# NanoTrac.net
KiCad netlist of a schematic drawn in EAGLE
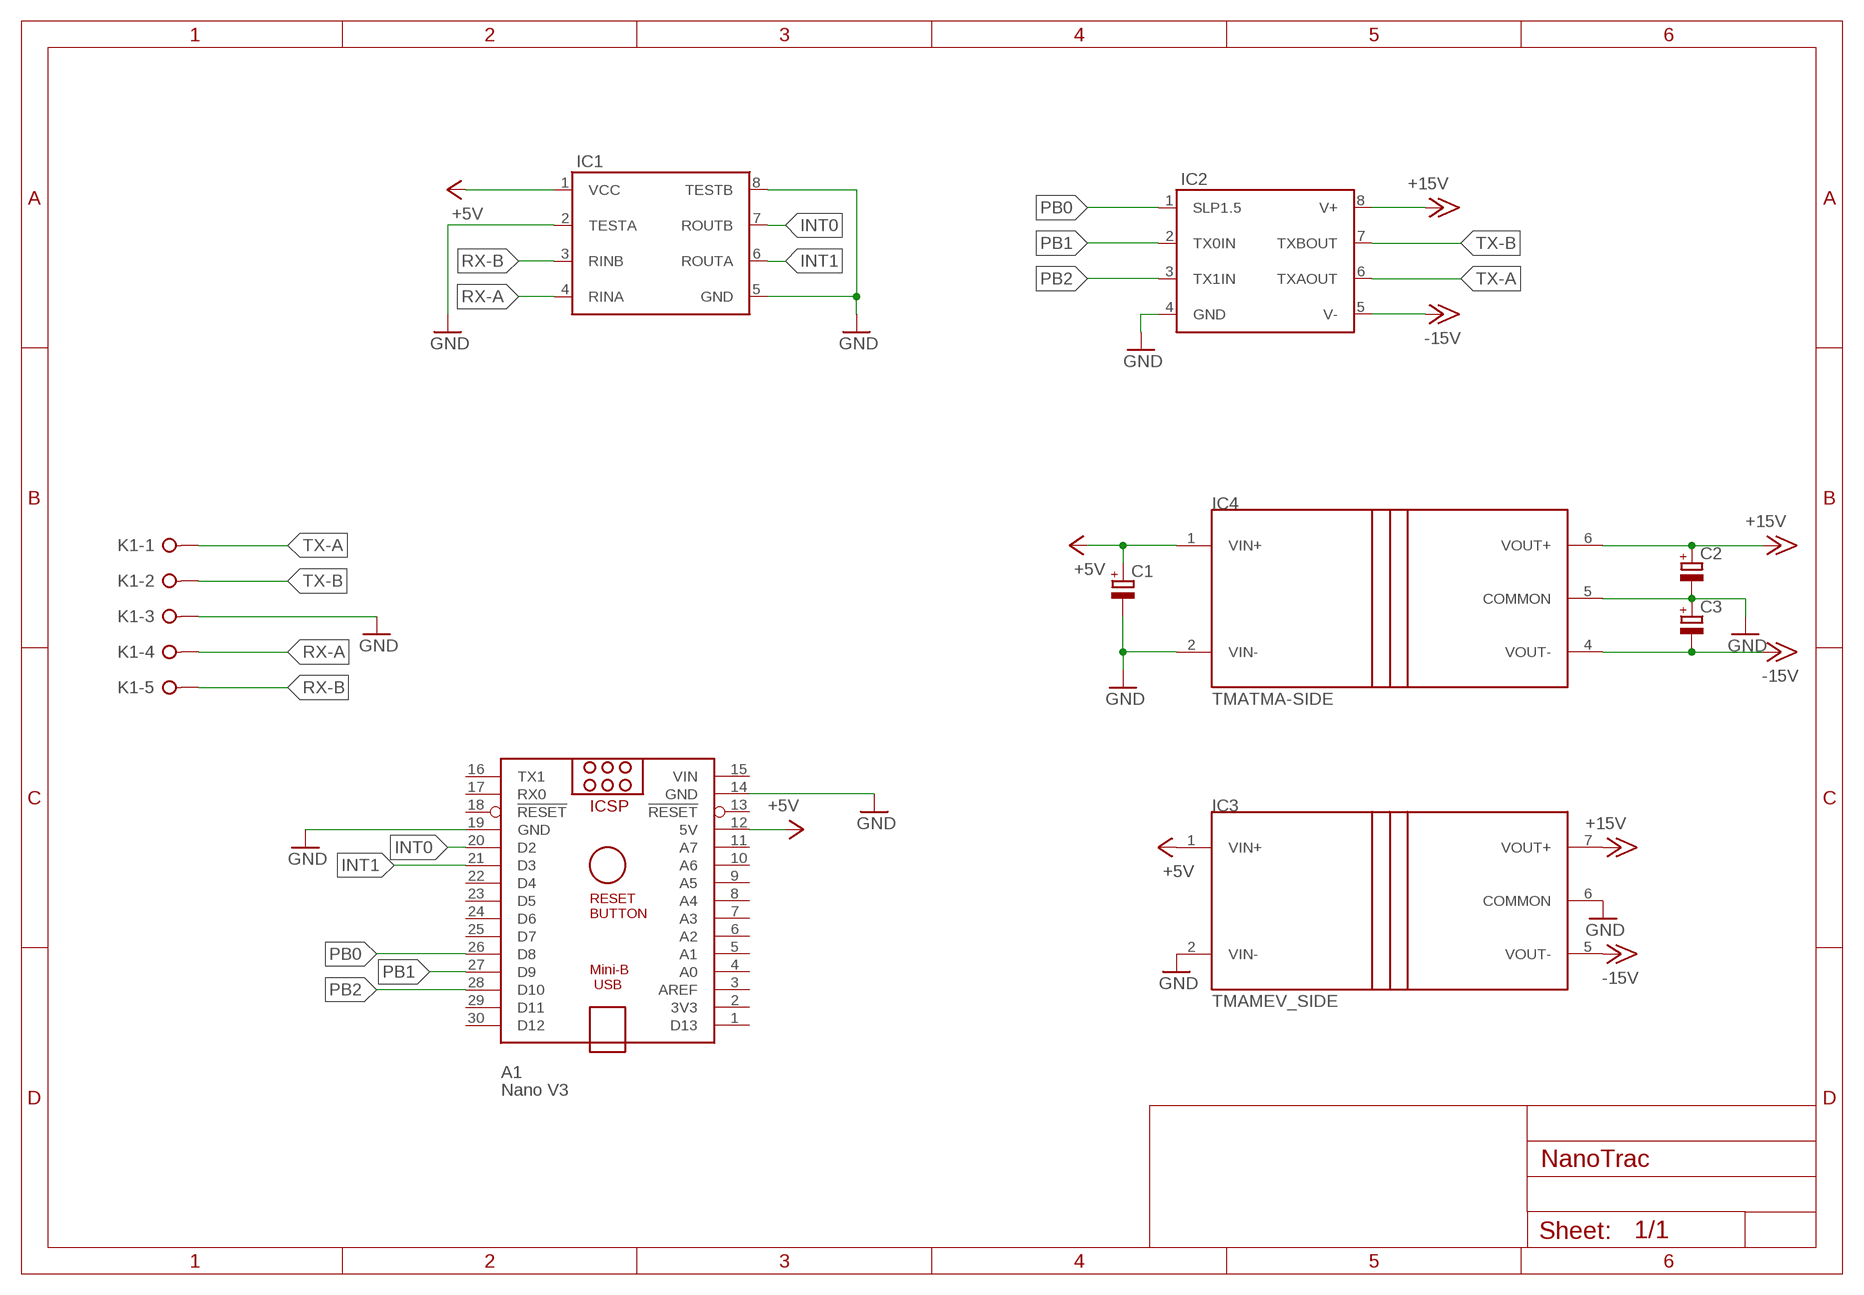
[diagram p0: schematic, sheet 1]

(export (version "E")
  (design (tool "Eeschema 10.0.6"))
  (components
    (comp (ref "A1")
      (value "Nano V3")
      (footprint "eagle-import:ARDUINO_NANO")
      (libsource (lib "eagle-import") (part "ARDUINO_NANO"))
    )
    (comp (ref "C1")
      (value "CPOL-EUE2-4")
      (footprint "eagle-import:E2-4")
      (libsource (lib "eagle-import") (part "CPOL-EUE2-4"))
    )
    (comp (ref "C2")
      (value "CPOL-EUE2-4")
      (footprint "eagle-import:E2-4")
      (libsource (lib "eagle-import") (part "CPOL-EUE2-4"))
    )
    (comp (ref "C3")
      (value "CPOL-EUE2-4")
      (footprint "eagle-import:E2-4")
      (libsource (lib "eagle-import") (part "CPOL-EUE2-4"))
    )
    (comp (ref "IC1")
      (value "HI-8588HN")
      (footprint "eagle-import:SOIC8")
      (libsource (lib "eagle-import") (part "HI-8588HN"))
    )
    (comp (ref "IC2")
      (value "HI-8586HN")
      (footprint "eagle-import:SOIC8")
      (libsource (lib "eagle-import") (part "HI-8586HN"))
    )
    (comp (ref "IC3")
      (value "TMAMEV_SIDE")
      (footprint "eagle-import:MEV_SIP7_SIDE")
      (libsource (lib "eagle-import") (part "TMAMEV_SIDE"))
    )
    (comp (ref "IC4")
      (value "TMATMA-SIDE")
      (footprint "eagle-import:SIP7_SIDE")
      (libsource (lib "eagle-import") (part "TMATMA-SIDE"))
    )
    (comp (ref "K1")
      (value "W237-05P")
      (footprint "eagle-import:W237-5P")
      (libsource (lib "eagle-import") (part "W237-05P"))
    )
  )
  (nets
    (net (code "1") (name "+5V") (class "Default")
      (node (ref "A1") (pin "12") (pinfunction "5V_12") (pintype "power_in"))
      (node (ref "C1") (pin "+") (pinfunction "+_+") (pintype "passive"))
      (node (ref "IC1") (pin "1") (pinfunction "VCC_1") (pintype "power_in"))
      (node (ref "IC3") (pin "1") (pinfunction "VIN+_1") (pintype "power_in"))
      (node (ref "IC4") (pin "1") (pinfunction "VIN+_1") (pintype "power_in"))
    )
    (net (code "2") (name "+15V") (class "Default")
      (node (ref "C2") (pin "+") (pinfunction "+_+") (pintype "passive"))
      (node (ref "IC2") (pin "8") (pinfunction "V+_8") (pintype "power_in"))
      (node (ref "IC3") (pin "7") (pinfunction "VOUT+_7") (pintype "power_in"))
      (node (ref "IC4") (pin "6") (pinfunction "VOUT+_6") (pintype "power_in"))
    )
    (net (code "3") (name "-15V") (class "Default")
      (node (ref "C3") (pin "-") (pinfunction "-_-") (pintype "passive"))
      (node (ref "IC2") (pin "5") (pinfunction "V-_5") (pintype "power_in"))
      (node (ref "IC3") (pin "5") (pinfunction "VOUT-_5") (pintype "power_in"))
      (node (ref "IC4") (pin "4") (pinfunction "VOUT-_4") (pintype "power_in"))
    )
    (net (code "4") (name "/VIN") (class "Default")
      (node (ref "A1") (pin "15") (pinfunction "VIN_15") (pintype "power_in"))
    )
    (net (code "5") (name "GND") (class "Default")
      (node (ref "A1") (pin "14") (pinfunction "GND_14") (pintype "power_in"))
      (node (ref "A1") (pin "19") (pinfunction "GND_19") (pintype "power_in"))
      (node (ref "C1") (pin "-") (pinfunction "-_-") (pintype "passive"))
      (node (ref "C2") (pin "-") (pinfunction "-_-") (pintype "passive"))
      (node (ref "C3") (pin "+") (pinfunction "+_+") (pintype "passive"))
      (node (ref "IC1") (pin "2") (pinfunction "TESTA_2") (pintype "input"))
      (node (ref "IC1") (pin "5") (pinfunction "GND_5") (pintype "passive"))
      (node (ref "IC1") (pin "8") (pinfunction "TESTB_8") (pintype "input"))
      (node (ref "IC2") (pin "4") (pinfunction "GND_4") (pintype "passive"))
      (node (ref "IC3") (pin "2") (pinfunction "VIN-_2") (pintype "power_in"))
      (node (ref "IC3") (pin "6") (pinfunction "COMMON_6") (pintype "power_in"))
      (node (ref "IC4") (pin "2") (pinfunction "VIN-_2") (pintype "power_in"))
      (node (ref "IC4") (pin "5") (pinfunction "COMMON_5") (pintype "power_in"))
      (node (ref "K1") (pin "3") (pinfunction "KL_3") (pintype "passive"))
    )
    (net (code "6") (name "INT0") (class "Default")
      (node (ref "A1") (pin "20") (pinfunction "D2_20") (pintype "bidirectional"))
      (node (ref "IC1") (pin "7") (pinfunction "ROUTB_7") (pintype "output"))
    )
    (net (code "7") (name "INT1") (class "Default")
      (node (ref "A1") (pin "21") (pinfunction "D3_21") (pintype "bidirectional"))
      (node (ref "IC1") (pin "6") (pinfunction "ROUTA_6") (pintype "output"))
    )
    (net (code "8") (name "PB0") (class "Default")
      (node (ref "A1") (pin "26") (pinfunction "D8_26") (pintype "bidirectional"))
      (node (ref "IC2") (pin "1") (pinfunction "SLP1.5_1") (pintype "input"))
    )
    (net (code "9") (name "PB1") (class "Default")
      (node (ref "A1") (pin "27") (pinfunction "D9_27") (pintype "bidirectional"))
      (node (ref "IC2") (pin "2") (pinfunction "TX0IN_2") (pintype "input"))
    )
    (net (code "10") (name "PB2") (class "Default")
      (node (ref "A1") (pin "28") (pinfunction "D10_28") (pintype "bidirectional"))
      (node (ref "IC2") (pin "3") (pinfunction "TX1IN_3") (pintype "input"))
    )
    (net (code "11") (name "RX-A") (class "Default")
      (node (ref "IC1") (pin "4") (pinfunction "RINA_4") (pintype "input"))
      (node (ref "K1") (pin "4") (pinfunction "KL_4") (pintype "passive"))
    )
    (net (code "12") (name "RX-B") (class "Default")
      (node (ref "IC1") (pin "3") (pinfunction "RINB_3") (pintype "input"))
      (node (ref "K1") (pin "5") (pinfunction "KL_5") (pintype "passive"))
    )
    (net (code "13") (name "TX-A") (class "Default")
      (node (ref "IC2") (pin "6") (pinfunction "TXAOUT_6") (pintype "output"))
      (node (ref "K1") (pin "1") (pinfunction "KL_1") (pintype "passive"))
    )
    (net (code "14") (name "TX-B") (class "Default")
      (node (ref "IC2") (pin "7") (pinfunction "TXBOUT_7") (pintype "output"))
      (node (ref "K1") (pin "2") (pinfunction "KL_2") (pintype "passive"))
    )
    (net (code "15") (name "unconnected-(A1-3V3-Pad2)") (class "Default")
      (node (ref "A1") (pin "2") (pinfunction "3V3_2") (pintype "output"))
    )
    (net (code "16") (name "unconnected-(A1-A0-Pad4)") (class "Default")
      (node (ref "A1") (pin "4") (pinfunction "A0_4") (pintype "bidirectional"))
    )
    (net (code "17") (name "unconnected-(A1-A1-Pad5)") (class "Default")
      (node (ref "A1") (pin "5") (pinfunction "A1_5") (pintype "bidirectional"))
    )
    (net (code "18") (name "unconnected-(A1-A2-Pad6)") (class "Default")
      (node (ref "A1") (pin "6") (pinfunction "A2_6") (pintype "bidirectional"))
    )
    (net (code "19") (name "unconnected-(A1-A3-Pad7)") (class "Default")
      (node (ref "A1") (pin "7") (pinfunction "A3_7") (pintype "bidirectional"))
    )
    (net (code "20") (name "unconnected-(A1-A4-Pad8)") (class "Default")
      (node (ref "A1") (pin "8") (pinfunction "A4_8") (pintype "bidirectional"))
    )
    (net (code "21") (name "unconnected-(A1-A5-Pad9)") (class "Default")
      (node (ref "A1") (pin "9") (pinfunction "A5_9") (pintype "bidirectional"))
    )
    (net (code "22") (name "unconnected-(A1-A6-Pad10)") (class "Default")
      (node (ref "A1") (pin "10") (pinfunction "A6_10") (pintype "bidirectional"))
    )
    (net (code "23") (name "unconnected-(A1-A7-Pad11)") (class "Default")
      (node (ref "A1") (pin "11") (pinfunction "A7_11") (pintype "bidirectional"))
    )
    (net (code "24") (name "unconnected-(A1-AREF-Pad3)") (class "Default")
      (node (ref "A1") (pin "3") (pinfunction "AREF_3") (pintype "input"))
    )
    (net (code "25") (name "unconnected-(A1-D4-Pad22)") (class "Default")
      (node (ref "A1") (pin "22") (pinfunction "D4_22") (pintype "bidirectional"))
    )
    (net (code "26") (name "unconnected-(A1-D5-Pad23)") (class "Default")
      (node (ref "A1") (pin "23") (pinfunction "D5_23") (pintype "bidirectional"))
    )
    (net (code "27") (name "unconnected-(A1-D6-Pad24)") (class "Default")
      (node (ref "A1") (pin "24") (pinfunction "D6_24") (pintype "bidirectional"))
    )
    (net (code "28") (name "unconnected-(A1-D7-Pad25)") (class "Default")
      (node (ref "A1") (pin "25") (pinfunction "D7_25") (pintype "bidirectional"))
    )
    (net (code "29") (name "unconnected-(A1-D11-Pad29)") (class "Default")
      (node (ref "A1") (pin "29") (pinfunction "D11_29") (pintype "bidirectional"))
    )
    (net (code "30") (name "unconnected-(A1-D12-Pad30)") (class "Default")
      (node (ref "A1") (pin "30") (pinfunction "D12_30") (pintype "bidirectional"))
    )
    (net (code "31") (name "unconnected-(A1-D13-Pad1)") (class "Default")
      (node (ref "A1") (pin "1") (pinfunction "D13_1") (pintype "bidirectional"))
    )
    (net (code "32") (name "unconnected-(A1-RX0-Pad17)") (class "Default")
      (node (ref "A1") (pin "17") (pinfunction "RX0_17") (pintype "bidirectional"))
    )
    (net (code "33") (name "unconnected-(A1-TX1-Pad16)") (class "Default")
      (node (ref "A1") (pin "16") (pinfunction "TX1_16") (pintype "bidirectional"))
    )
    (net (code "34") (name "unconnected-(A1-~{RESET}-Pad13)") (class "Default")
      (node (ref "A1") (pin "13") (pinfunction "~{RESET}_13") (pintype "input"))
    )
    (net (code "35") (name "unconnected-(A1-~{RESET}-Pad18)") (class "Default")
      (node (ref "A1") (pin "18") (pinfunction "~{RESET}_18") (pintype "input"))
    )
  )
)
